# SH08-PWR1.net
KiCad netlist of a schematic drawn in Altium Designer
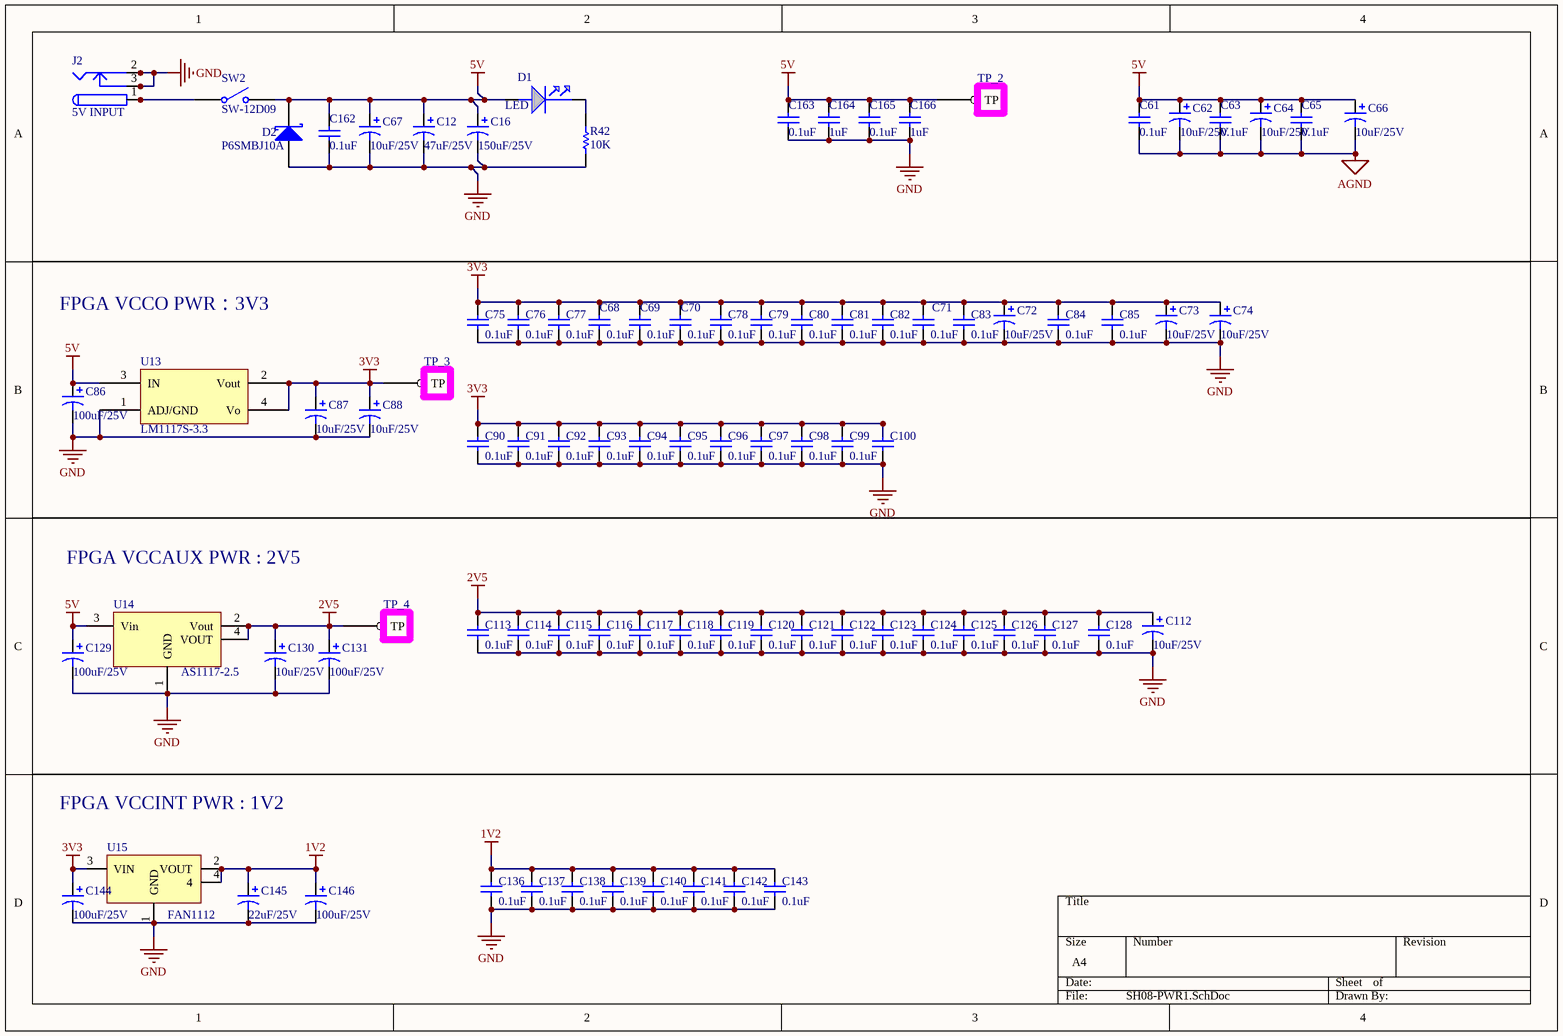
[diagram p0: SH08-PWR1.SchDoc]

(export (version "E")
  (design (tool "Eeschema 10.0.6"))
  (components
    (comp (ref "C12")
      (value "47uF/25V")
      (footprint "1210[3528]")
      (description "Polarized Capacitor (Radial)")
      (fields (field (name "Comment") "Cap Pol,47uF/25V,1210") (field (name "PUBLISHER") "Altium Limited"))
      (libsource (lib "Miscellaneous Devices") (part "Cap Pol1"))
    )
    (comp (ref "C16")
      (value "150uF/25V")
      (footprint "7343")
      (description "Polarized Capacitor (Radial)")
      (fields (field (name "Comment") "Cap Pol,150uF/25V,7343") (field (name "PUBLISHER") "Altium Limited"))
      (libsource (lib "Miscellaneous Devices") (part "Cap Pol1"))
    )
    (comp (ref "C61")
      (value "0.1uF")
      (footprint "1608[0603]")
      (description "Capacitor")
      (fields (field (name "Comment") "Cap,0.1uF/0603") (field (name "PUBLISHER") "Altium Limited"))
      (libsource (lib "Miscellaneous Devices") (part "Cap"))
    )
    (comp (ref "C62")
      (value "10uF/25V")
      (footprint "1206[3216]")
      (description "Polarized Capacitor (Radial)")
      (fields (field (name "Comment") "Cap Pol,10uF/25V,1206") (field (name "PUBLISHER") "Altium Limited"))
      (libsource (lib "Miscellaneous Devices") (part "Cap Pol1"))
    )
    (comp (ref "C63")
      (value "0.1uF")
      (footprint "1608[0603]")
      (description "Capacitor")
      (fields (field (name "Comment") "Cap,0.1uF/0603") (field (name "PUBLISHER") "Altium Limited"))
      (libsource (lib "Miscellaneous Devices") (part "Cap"))
    )
    (comp (ref "C64")
      (value "10uF/25V")
      (footprint "1206[3216]")
      (description "Polarized Capacitor (Radial)")
      (fields (field (name "Comment") "Cap Pol,10uF/25V,1206") (field (name "PUBLISHER") "Altium Limited"))
      (libsource (lib "Miscellaneous Devices") (part "Cap Pol1"))
    )
    (comp (ref "C65")
      (value "0.1uF")
      (footprint "1608[0603]")
      (description "Capacitor")
      (fields (field (name "Comment") "Cap,0.1uF/0603") (field (name "PUBLISHER") "Altium Limited"))
      (libsource (lib "Miscellaneous Devices") (part "Cap"))
    )
    (comp (ref "C66")
      (value "10uF/25V")
      (footprint "1206[3216]")
      (description "Polarized Capacitor (Radial)")
      (fields (field (name "Comment") "Cap Pol,10uF/25V,1206") (field (name "PUBLISHER") "Altium Limited"))
      (libsource (lib "Miscellaneous Devices") (part "Cap Pol1"))
    )
    (comp (ref "C67")
      (value "10uF/25V")
      (footprint "1206[3216]")
      (description "Polarized Capacitor (Radial)")
      (fields (field (name "Comment") "Cap Pol,10uF/25V,1206") (field (name "PUBLISHER") "Altium Limited"))
      (libsource (lib "Miscellaneous Devices") (part "Cap Pol1"))
    )
    (comp (ref "C68")
      (value "0.1uF")
      (footprint "1608[0603]")
      (description "Capacitor")
      (fields (field (name "Comment") "Cap,0.1uF/0603") (field (name "PUBLISHER") "Altium Limited"))
      (libsource (lib "Miscellaneous Devices") (part "Cap"))
    )
    (comp (ref "C69")
      (value "0.1uF")
      (footprint "1608[0603]")
      (description "Capacitor")
      (fields (field (name "Comment") "Cap,0.1uF/0603") (field (name "PUBLISHER") "Altium Limited"))
      (libsource (lib "Miscellaneous Devices") (part "Cap"))
    )
    (comp (ref "C70")
      (value "0.1uF")
      (footprint "1608[0603]")
      (description "Capacitor")
      (fields (field (name "Comment") "Cap,0.1uF/0603") (field (name "PUBLISHER") "Altium Limited"))
      (libsource (lib "Miscellaneous Devices") (part "Cap"))
    )
    (comp (ref "C71")
      (value "0.1uF")
      (footprint "1608[0603]")
      (description "Capacitor")
      (fields (field (name "Comment") "Cap,0.1uF/0603") (field (name "PUBLISHER") "Altium Limited"))
      (libsource (lib "Miscellaneous Devices") (part "Cap"))
    )
    (comp (ref "C72")
      (value "10uF/25V")
      (footprint "1206[3216]")
      (description "Polarized Capacitor (Radial)")
      (fields (field (name "Comment") "Cap Pol,10uF/25V,1206") (field (name "PUBLISHER") "Altium Limited"))
      (libsource (lib "Miscellaneous Devices") (part "Cap Pol1"))
    )
    (comp (ref "C73")
      (value "10uF/25V")
      (footprint "1206[3216]")
      (description "Polarized Capacitor (Radial)")
      (fields (field (name "Comment") "Cap Pol,10uF/25V,1206") (field (name "PUBLISHER") "Altium Limited"))
      (libsource (lib "Miscellaneous Devices") (part "Cap Pol1"))
    )
    (comp (ref "C74")
      (value "10uF/25V")
      (footprint "1206[3216]")
      (description "Polarized Capacitor (Radial)")
      (fields (field (name "Comment") "Cap Pol,10uF/25V,1206") (field (name "PUBLISHER") "Altium Limited"))
      (libsource (lib "Miscellaneous Devices") (part "Cap Pol1"))
    )
    (comp (ref "C75")
      (value "0.1uF")
      (footprint "1608[0603]")
      (description "Capacitor")
      (fields (field (name "Comment") "Cap,0.1uF/0603") (field (name "PUBLISHER") "Altium Limited"))
      (libsource (lib "Miscellaneous Devices") (part "Cap"))
    )
    (comp (ref "C76")
      (value "0.1uF")
      (footprint "1608[0603]")
      (description "Capacitor")
      (fields (field (name "Comment") "Cap,0.1uF/0603") (field (name "PUBLISHER") "Altium Limited"))
      (libsource (lib "Miscellaneous Devices") (part "Cap"))
    )
    (comp (ref "C77")
      (value "0.1uF")
      (footprint "1608[0603]")
      (description "Capacitor")
      (fields (field (name "Comment") "Cap,0.1uF/0603") (field (name "PUBLISHER") "Altium Limited"))
      (libsource (lib "Miscellaneous Devices") (part "Cap"))
    )
    (comp (ref "C78")
      (value "0.1uF")
      (footprint "1608[0603]")
      (description "Capacitor")
      (fields (field (name "Comment") "Cap,0.1uF/0603") (field (name "PUBLISHER") "Altium Limited"))
      (libsource (lib "Miscellaneous Devices") (part "Cap"))
    )
    (comp (ref "C79")
      (value "0.1uF")
      (footprint "1608[0603]")
      (description "Capacitor")
      (fields (field (name "Comment") "Cap,0.1uF/0603") (field (name "PUBLISHER") "Altium Limited"))
      (libsource (lib "Miscellaneous Devices") (part "Cap"))
    )
    (comp (ref "C80")
      (value "0.1uF")
      (footprint "1608[0603]")
      (description "Capacitor")
      (fields (field (name "Comment") "Cap,0.1uF/0603") (field (name "PUBLISHER") "Altium Limited"))
      (libsource (lib "Miscellaneous Devices") (part "Cap"))
    )
    (comp (ref "C81")
      (value "0.1uF")
      (footprint "1608[0603]")
      (description "Capacitor")
      (fields (field (name "Comment") "Cap,0.1uF/0603") (field (name "PUBLISHER") "Altium Limited"))
      (libsource (lib "Miscellaneous Devices") (part "Cap"))
    )
    (comp (ref "C82")
      (value "0.1uF")
      (footprint "1608[0603]")
      (description "Capacitor")
      (fields (field (name "Comment") "Cap,0.1uF/0603") (field (name "PUBLISHER") "Altium Limited"))
      (libsource (lib "Miscellaneous Devices") (part "Cap"))
    )
    (comp (ref "C83")
      (value "0.1uF")
      (footprint "1608[0603]")
      (description "Capacitor")
      (fields (field (name "Comment") "Cap,0.1uF/0603") (field (name "PUBLISHER") "Altium Limited"))
      (libsource (lib "Miscellaneous Devices") (part "Cap"))
    )
    (comp (ref "C84")
      (value "0.1uF")
      (footprint "1608[0603]")
      (description "Capacitor")
      (fields (field (name "Comment") "Cap,0.1uF/0603") (field (name "PUBLISHER") "Altium Limited"))
      (libsource (lib "Miscellaneous Devices") (part "Cap"))
    )
    (comp (ref "C85")
      (value "0.1uF")
      (footprint "1608[0603]")
      (description "Capacitor")
      (fields (field (name "Comment") "Cap,0.1uF/0603") (field (name "PUBLISHER") "Altium Limited"))
      (libsource (lib "Miscellaneous Devices") (part "Cap"))
    )
    (comp (ref "C86")
      (value "100uF/25V")
      (footprint "1210[3528]")
      (description "Polarized Capacitor (Radial)")
      (fields (field (name "Comment") "Cap Pol,100uF/25V,1210") (field (name "PUBLISHER") "Altium Limited"))
      (libsource (lib "Miscellaneous Devices") (part "Cap Pol1"))
    )
    (comp (ref "C87")
      (value "10uF/25V")
      (footprint "1206[3216]")
      (description "Polarized Capacitor (Radial)")
      (fields (field (name "Comment") "Cap Pol,10uF/25V,1206") (field (name "PUBLISHER") "Altium Limited"))
      (libsource (lib "Miscellaneous Devices") (part "Cap Pol1"))
    )
    (comp (ref "C88")
      (value "10uF/25V")
      (footprint "1206[3216]")
      (description "Polarized Capacitor (Radial)")
      (fields (field (name "Comment") "Cap Pol,10uF/25V,1206") (field (name "PUBLISHER") "Altium Limited"))
      (libsource (lib "Miscellaneous Devices") (part "Cap Pol1"))
    )
    (comp (ref "C90")
      (value "0.1uF")
      (footprint "1608[0603]")
      (description "Capacitor")
      (fields (field (name "Comment") "Cap,0.1uF/0603") (field (name "PUBLISHER") "Altium Limited"))
      (libsource (lib "Miscellaneous Devices") (part "Cap"))
    )
    (comp (ref "C91")
      (value "0.1uF")
      (footprint "1608[0603]")
      (description "Capacitor")
      (fields (field (name "Comment") "Cap,0.1uF/0603") (field (name "PUBLISHER") "Altium Limited"))
      (libsource (lib "Miscellaneous Devices") (part "Cap"))
    )
    (comp (ref "C92")
      (value "0.1uF")
      (footprint "1608[0603]")
      (description "Capacitor")
      (fields (field (name "Comment") "Cap,0.1uF/0603") (field (name "PUBLISHER") "Altium Limited"))
      (libsource (lib "Miscellaneous Devices") (part "Cap"))
    )
    (comp (ref "C93")
      (value "0.1uF")
      (footprint "1608[0603]")
      (description "Capacitor")
      (fields (field (name "Comment") "Cap,0.1uF/0603") (field (name "PUBLISHER") "Altium Limited"))
      (libsource (lib "Miscellaneous Devices") (part "Cap"))
    )
    (comp (ref "C94")
      (value "0.1uF")
      (footprint "1608[0603]")
      (description "Capacitor")
      (fields (field (name "Comment") "Cap,0.1uF/0603") (field (name "PUBLISHER") "Altium Limited"))
      (libsource (lib "Miscellaneous Devices") (part "Cap"))
    )
    (comp (ref "C95")
      (value "0.1uF")
      (footprint "1608[0603]")
      (description "Capacitor")
      (fields (field (name "Comment") "Cap,0.1uF/0603") (field (name "PUBLISHER") "Altium Limited"))
      (libsource (lib "Miscellaneous Devices") (part "Cap"))
    )
    (comp (ref "C96")
      (value "0.1uF")
      (footprint "1608[0603]")
      (description "Capacitor")
      (fields (field (name "Comment") "Cap,0.1uF/0603") (field (name "PUBLISHER") "Altium Limited"))
      (libsource (lib "Miscellaneous Devices") (part "Cap"))
    )
    (comp (ref "C97")
      (value "0.1uF")
      (footprint "1608[0603]")
      (description "Capacitor")
      (fields (field (name "Comment") "Cap,0.1uF/0603") (field (name "PUBLISHER") "Altium Limited"))
      (libsource (lib "Miscellaneous Devices") (part "Cap"))
    )
    (comp (ref "C98")
      (value "0.1uF")
      (footprint "1608[0603]")
      (description "Capacitor")
      (fields (field (name "Comment") "Cap,0.1uF/0603") (field (name "PUBLISHER") "Altium Limited"))
      (libsource (lib "Miscellaneous Devices") (part "Cap"))
    )
    (comp (ref "C99")
      (value "0.1uF")
      (footprint "1608[0603]")
      (description "Capacitor")
      (fields (field (name "Comment") "Cap,0.1uF/0603") (field (name "PUBLISHER") "Altium Limited"))
      (libsource (lib "Miscellaneous Devices") (part "Cap"))
    )
    (comp (ref "C100")
      (value "Cap,0.1uF/0603")
      (footprint "1608[0603]")
      (description "Capacitor")
      (fields (field (name "PUBLISHER") "Altium Limited"))
      (libsource (lib "Miscellaneous Devices") (part "Cap"))
    )
    (comp (ref "C112")
      (value "10uF/25V")
      (footprint "1206[3216]")
      (description "Polarized Capacitor (Radial)")
      (fields (field (name "Comment") "Cap Pol,10uF/25V,1206") (field (name "PUBLISHER") "Altium Limited"))
      (libsource (lib "Miscellaneous Devices") (part "Cap Pol1"))
    )
    (comp (ref "C113")
      (value "0.1uF")
      (footprint "1608[0603]")
      (description "Capacitor")
      (fields (field (name "Comment") "Cap,0.1uF/0603") (field (name "PUBLISHER") "Altium Limited"))
      (libsource (lib "Miscellaneous Devices") (part "Cap"))
    )
    (comp (ref "C114")
      (value "0.1uF")
      (footprint "1608[0603]")
      (description "Capacitor")
      (fields (field (name "Comment") "Cap,0.1uF/0603") (field (name "PUBLISHER") "Altium Limited"))
      (libsource (lib "Miscellaneous Devices") (part "Cap"))
    )
    (comp (ref "C115")
      (value "0.1uF")
      (footprint "1608[0603]")
      (description "Capacitor")
      (fields (field (name "Comment") "Cap,0.1uF/0603") (field (name "PUBLISHER") "Altium Limited"))
      (libsource (lib "Miscellaneous Devices") (part "Cap"))
    )
    (comp (ref "C116")
      (value "0.1uF")
      (footprint "1608[0603]")
      (description "Capacitor")
      (fields (field (name "Comment") "Cap,0.1uF/0603") (field (name "PUBLISHER") "Altium Limited"))
      (libsource (lib "Miscellaneous Devices") (part "Cap"))
    )
    (comp (ref "C117")
      (value "0.1uF")
      (footprint "1608[0603]")
      (description "Capacitor")
      (fields (field (name "Comment") "Cap,0.1uF/0603") (field (name "PUBLISHER") "Altium Limited"))
      (libsource (lib "Miscellaneous Devices") (part "Cap"))
    )
    (comp (ref "C118")
      (value "0.1uF")
      (footprint "1608[0603]")
      (description "Capacitor")
      (fields (field (name "Comment") "Cap,0.1uF/0603") (field (name "PUBLISHER") "Altium Limited"))
      (libsource (lib "Miscellaneous Devices") (part "Cap"))
    )
    (comp (ref "C119")
      (value "0.1uF")
      (footprint "1608[0603]")
      (description "Capacitor")
      (fields (field (name "Comment") "Cap,0.1uF/0603") (field (name "PUBLISHER") "Altium Limited"))
      (libsource (lib "Miscellaneous Devices") (part "Cap"))
    )
    (comp (ref "C120")
      (value "0.1uF")
      (footprint "1608[0603]")
      (description "Capacitor")
      (fields (field (name "Comment") "Cap,0.1uF/0603") (field (name "PUBLISHER") "Altium Limited"))
      (libsource (lib "Miscellaneous Devices") (part "Cap"))
    )
    (comp (ref "C121")
      (value "0.1uF")
      (footprint "1608[0603]")
      (description "Capacitor")
      (fields (field (name "Comment") "Cap,0.1uF/0603") (field (name "PUBLISHER") "Altium Limited"))
      (libsource (lib "Miscellaneous Devices") (part "Cap"))
    )
    (comp (ref "C122")
      (value "0.1uF")
      (footprint "1608[0603]")
      (description "Capacitor")
      (fields (field (name "Comment") "Cap,0.1uF/0603") (field (name "PUBLISHER") "Altium Limited"))
      (libsource (lib "Miscellaneous Devices") (part "Cap"))
    )
    (comp (ref "C123")
      (value "0.1uF")
      (footprint "1608[0603]")
      (description "Capacitor")
      (fields (field (name "Comment") "Cap,0.1uF/0603") (field (name "PUBLISHER") "Altium Limited"))
      (libsource (lib "Miscellaneous Devices") (part "Cap"))
    )
    (comp (ref "C124")
      (value "0.1uF")
      (footprint "1608[0603]")
      (description "Capacitor")
      (fields (field (name "Comment") "Cap,0.1uF/0603") (field (name "PUBLISHER") "Altium Limited"))
      (libsource (lib "Miscellaneous Devices") (part "Cap"))
    )
    (comp (ref "C125")
      (value "0.1uF")
      (footprint "1608[0603]")
      (description "Capacitor")
      (fields (field (name "Comment") "Cap,0.1uF/0603") (field (name "PUBLISHER") "Altium Limited"))
      (libsource (lib "Miscellaneous Devices") (part "Cap"))
    )
    (comp (ref "C126")
      (value "0.1uF")
      (footprint "1608[0603]")
      (description "Capacitor")
      (fields (field (name "Comment") "Cap,0.1uF/0603") (field (name "PUBLISHER") "Altium Limited"))
      (libsource (lib "Miscellaneous Devices") (part "Cap"))
    )
    (comp (ref "C127")
      (value "0.1uF")
      (footprint "1608[0603]")
      (description "Capacitor")
      (fields (field (name "Comment") "Cap,0.1uF/0603") (field (name "PUBLISHER") "Altium Limited"))
      (libsource (lib "Miscellaneous Devices") (part "Cap"))
    )
    (comp (ref "C128")
      (value "0.1uF")
      (footprint "1608[0603]")
      (description "Capacitor")
      (fields (field (name "Comment") "Cap,0.1uF/0603") (field (name "PUBLISHER") "Altium Limited"))
      (libsource (lib "Miscellaneous Devices") (part "Cap"))
    )
    (comp (ref "C129")
      (value "100uF/25V")
      (footprint "1210[3528]")
      (description "Polarized Capacitor (Radial)")
      (fields (field (name "Comment") "Cap Pol,100uF/25V,1210") (field (name "PUBLISHER") "Altium Limited"))
      (libsource (lib "Miscellaneous Devices") (part "Cap Pol1"))
    )
    (comp (ref "C130")
      (value "10uF/25V")
      (footprint "1206[3216]")
      (description "Polarized Capacitor (Radial)")
      (fields (field (name "Comment") "Cap Pol,10uF/25V,1206") (field (name "PUBLISHER") "Altium Limited"))
      (libsource (lib "Miscellaneous Devices") (part "Cap Pol1"))
    )
    (comp (ref "C131")
      (value "100uF/25V")
      (footprint "1210[3528]")
      (description "Polarized Capacitor (Radial)")
      (fields (field (name "Comment") "Cap Pol,100uF/25V,1210") (field (name "PUBLISHER") "Altium Limited"))
      (libsource (lib "Miscellaneous Devices") (part "Cap Pol1"))
    )
    (comp (ref "C136")
      (value "0.1uF")
      (footprint "1608[0603]")
      (description "Capacitor")
      (fields (field (name "Comment") "Cap,0.1uF/0603") (field (name "PUBLISHER") "Altium Limited"))
      (libsource (lib "Miscellaneous Devices") (part "Cap"))
    )
    (comp (ref "C137")
      (value "0.1uF")
      (footprint "1608[0603]")
      (description "Capacitor")
      (fields (field (name "Comment") "Cap,0.1uF/0603") (field (name "PUBLISHER") "Altium Limited"))
      (libsource (lib "Miscellaneous Devices") (part "Cap"))
    )
    (comp (ref "C138")
      (value "0.1uF")
      (footprint "1608[0603]")
      (description "Capacitor")
      (fields (field (name "Comment") "Cap,0.1uF/0603") (field (name "PUBLISHER") "Altium Limited"))
      (libsource (lib "Miscellaneous Devices") (part "Cap"))
    )
    (comp (ref "C139")
      (value "0.1uF")
      (footprint "1608[0603]")
      (description "Capacitor")
      (fields (field (name "Comment") "Cap,0.1uF/0603") (field (name "PUBLISHER") "Altium Limited"))
      (libsource (lib "Miscellaneous Devices") (part "Cap"))
    )
    (comp (ref "C140")
      (value "0.1uF")
      (footprint "1608[0603]")
      (description "Capacitor")
      (fields (field (name "Comment") "Cap,0.1uF/0603") (field (name "PUBLISHER") "Altium Limited"))
      (libsource (lib "Miscellaneous Devices") (part "Cap"))
    )
    (comp (ref "C141")
      (value "0.1uF")
      (footprint "1608[0603]")
      (description "Capacitor")
      (fields (field (name "Comment") "Cap,0.1uF/0603") (field (name "PUBLISHER") "Altium Limited"))
      (libsource (lib "Miscellaneous Devices") (part "Cap"))
    )
    (comp (ref "C142")
      (value "0.1uF")
      (footprint "1608[0603]")
      (description "Capacitor")
      (fields (field (name "Comment") "Cap,0.1uF/0603") (field (name "PUBLISHER") "Altium Limited"))
      (libsource (lib "Miscellaneous Devices") (part "Cap"))
    )
    (comp (ref "C143")
      (value "0.1uF")
      (footprint "1608[0603]")
      (description "Capacitor")
      (fields (field (name "Comment") "Cap,0.1uF/0603") (field (name "PUBLISHER") "Altium Limited"))
      (libsource (lib "Miscellaneous Devices") (part "Cap"))
    )
    (comp (ref "C144")
      (value "100uF/25V")
      (footprint "1210[3528]")
      (description "Polarized Capacitor (Radial)")
      (fields (field (name "Comment") "Cap Pol,100uF/25V,1210") (field (name "PUBLISHER") "Altium Limited"))
      (libsource (lib "Miscellaneous Devices") (part "Cap Pol1"))
    )
    (comp (ref "C145")
      (value "22uF/25V")
      (footprint "1210[3528]")
      (description "Polarized Capacitor (Radial)")
      (fields (field (name "Comment") "Cap Pol,22uF/25V,1210") (field (name "PUBLISHER") "Altium Limited"))
      (libsource (lib "Miscellaneous Devices") (part "Cap Pol1"))
    )
    (comp (ref "C146")
      (value "100uF/25V")
      (footprint "1210[3528]")
      (description "Polarized Capacitor (Radial)")
      (fields (field (name "Comment") "Cap Pol,100uF/25V,1210") (field (name "PUBLISHER") "Altium Limited"))
      (libsource (lib "Miscellaneous Devices") (part "Cap Pol1"))
    )
    (comp (ref "C162")
      (value "0.1uF")
      (footprint "1608[0603]")
      (description "Capacitor")
      (fields (field (name "Comment") "Cap,0.1uF/0603") (field (name "PUBLISHER") "Altium Limited"))
      (libsource (lib "Miscellaneous Devices") (part "Cap"))
    )
    (comp (ref "C163")
      (value "0.1uF")
      (footprint "1608[0603]")
      (description "Capacitor")
      (fields (field (name "Comment") "Cap,0.1uF/0603") (field (name "PUBLISHER") "Altium Limited"))
      (libsource (lib "Miscellaneous Devices") (part "Cap"))
    )
    (comp (ref "C164")
      (value "1uF")
      (footprint "2012[0805]")
      (description "Capacitor")
      (fields (field (name "Comment") "Cap,1uF/0805") (field (name "PUBLISHER") "Altium Limited"))
      (libsource (lib "Miscellaneous Devices") (part "Cap"))
    )
    (comp (ref "C165")
      (value "0.1uF")
      (footprint "1608[0603]")
      (description "Capacitor")
      (fields (field (name "Comment") "Cap,0.1uF/0603") (field (name "PUBLISHER") "Altium Limited"))
      (libsource (lib "Miscellaneous Devices") (part "Cap"))
    )
    (comp (ref "C166")
      (value "1uF")
      (footprint "2012[0805]")
      (description "Capacitor")
      (fields (field (name "Comment") "Cap,1uF/0805") (field (name "PUBLISHER") "Altium Limited"))
      (libsource (lib "Miscellaneous Devices") (part "Cap"))
    )
    (comp (ref "D1")
      (value "LED")
      (footprint "Laser-LiuXin:2012[0805] - LED")
      (libsource (lib "Mylibrary") (part "LED"))
    )
    (comp (ref "D2")
      (value "P6SMBJ10A")
      (footprint "Laser-LiuXin:SMBJ10A_DIOM4336X24N")
      (description "Schottky Rectifier")
      (fields (field (name "PUBLISHER") "Altium Limited"))
      (libsource (lib "Miscellaneous Devices") (part "Diode 11DQ03"))
    )
    (comp (ref "J2")
      (value "5V INPUT")
      (footprint "Laser-LiuXin:IF_KLD-0202")
      (description "Low Voltage Power Supply Connector")
      (fields (field (name "PUBLISHER") "Altium Limited"))
      (libsource (lib "Miscellaneous Connectors") (part "PWR2.5"))
    )
    (comp (ref "R42")
      (value "10K")
      (footprint "Laser-LiuXin:1608[0603]")
      (description "Resistor")
      (fields (field (name "Comment") "Res,10K/0603") (field (name "PUBLISHER") "Altium Limited"))
      (libsource (lib "Miscellaneous Devices") (part "Res1"))
    )
    (comp (ref "SW2")
      (value "SW-12D09")
      (footprint "SW_SD12D09")
      (description "Single-Pole, Single-Throw Switch")
      (fields (field (name "PUBLISHER") "Altium Limited"))
      (libsource (lib "Miscellaneous Devices") (part "SW-SPST"))
    )
    (comp (ref "TP_2") (value "5V") (footprint "MYTP") (libsource (lib "*") (part "TEST POINT_0")))
    (comp (ref "TP_3") (value "3V3") (footprint "MYTP") (libsource (lib "*") (part "TEST POINT_0")))
    (comp (ref "TP_4") (value "2V5") (footprint "MYTP") (libsource (lib "*") (part "TEST POINT_0")))
    (comp (ref "U13")
      (value "LM1117S-3.3")
      (footprint "Laser-LiuXin:TO-263-3SMD")
      (libsource (lib "Laser-LiuXin") (part "PWR_LM1117S-3.3"))
    )
    (comp (ref "U14")
      (value "AS1117-2.5")
      (footprint "SOT223P700X180-4N")
      (libsource (lib "Mylibrary") (part "VOLTREG"))
    )
    (comp (ref "U15")
      (value "FAN1112")
      (footprint "SOT-223(FAN1112)")
      (libsource (lib "PCB_Project_FPGA_aquisition") (part "FAN1112"))
    )
  )
  (nets
    (net (code "1") (name "1V2") (class "Default")
      (node (ref "C136") (pin "2") (pinfunction "2_2") (pintype "passive"))
      (node (ref "C137") (pin "2") (pinfunction "2_2") (pintype "passive"))
      (node (ref "C138") (pin "2") (pinfunction "2_2") (pintype "passive"))
      (node (ref "C139") (pin "2") (pinfunction "2_2") (pintype "passive"))
      (node (ref "C140") (pin "2") (pinfunction "2_2") (pintype "passive"))
      (node (ref "C141") (pin "2") (pinfunction "2_2") (pintype "passive"))
      (node (ref "C142") (pin "2") (pinfunction "2_2") (pintype "passive"))
      (node (ref "C143") (pin "2") (pinfunction "2_2") (pintype "passive"))
      (node (ref "C145") (pin "1") (pinfunction "1_1") (pintype "passive"))
      (node (ref "C146") (pin "1") (pinfunction "1_1") (pintype "passive"))
      (node (ref "U15") (pin "2") (pinfunction "VOUT_2") (pintype "passive"))
      (node (ref "U15") (pin "4") (pinfunction "4_4") (pintype "passive"))
    )
    (net (code "2") (name "2V5") (class "Default")
      (node (ref "C112") (pin "1") (pinfunction "1_1") (pintype "passive"))
      (node (ref "C113") (pin "2") (pinfunction "2_2") (pintype "passive"))
      (node (ref "C114") (pin "2") (pinfunction "2_2") (pintype "passive"))
      (node (ref "C115") (pin "2") (pinfunction "2_2") (pintype "passive"))
      (node (ref "C116") (pin "2") (pinfunction "2_2") (pintype "passive"))
      (node (ref "C117") (pin "2") (pinfunction "2_2") (pintype "passive"))
      (node (ref "C118") (pin "2") (pinfunction "2_2") (pintype "passive"))
      (node (ref "C119") (pin "2") (pinfunction "2_2") (pintype "passive"))
      (node (ref "C120") (pin "2") (pinfunction "2_2") (pintype "passive"))
      (node (ref "C121") (pin "2") (pinfunction "2_2") (pintype "passive"))
      (node (ref "C122") (pin "2") (pinfunction "2_2") (pintype "passive"))
      (node (ref "C123") (pin "2") (pinfunction "2_2") (pintype "passive"))
      (node (ref "C124") (pin "2") (pinfunction "2_2") (pintype "passive"))
      (node (ref "C125") (pin "2") (pinfunction "2_2") (pintype "passive"))
      (node (ref "C126") (pin "2") (pinfunction "2_2") (pintype "passive"))
      (node (ref "C127") (pin "2") (pinfunction "2_2") (pintype "passive"))
      (node (ref "C128") (pin "2") (pinfunction "2_2") (pintype "passive"))
      (node (ref "C130") (pin "1") (pinfunction "1_1") (pintype "passive"))
      (node (ref "C131") (pin "1") (pinfunction "1_1") (pintype "passive"))
      (node (ref "TP_4") (pin "1") (pinfunction "TP_1") (pintype "passive"))
      (node (ref "U14") (pin "2") (pinfunction "Vout_2") (pintype "passive"))
      (node (ref "U14") (pin "4") (pinfunction "VOUT_4") (pintype "passive"))
    )
    (net (code "3") (name "3V3") (class "Default")
      (node (ref "C100") (pin "2") (pinfunction "2_2") (pintype "passive"))
      (node (ref "C144") (pin "1") (pinfunction "1_1") (pintype "passive"))
      (node (ref "C68") (pin "2") (pinfunction "2_2") (pintype "passive"))
      (node (ref "C69") (pin "2") (pinfunction "2_2") (pintype "passive"))
      (node (ref "C70") (pin "2") (pinfunction "2_2") (pintype "passive"))
      (node (ref "C71") (pin "2") (pinfunction "2_2") (pintype "passive"))
      (node (ref "C72") (pin "1") (pinfunction "1_1") (pintype "passive"))
      (node (ref "C73") (pin "1") (pinfunction "1_1") (pintype "passive"))
      (node (ref "C74") (pin "1") (pinfunction "1_1") (pintype "passive"))
      (node (ref "C75") (pin "2") (pinfunction "2_2") (pintype "passive"))
      (node (ref "C76") (pin "2") (pinfunction "2_2") (pintype "passive"))
      (node (ref "C77") (pin "2") (pinfunction "2_2") (pintype "passive"))
      (node (ref "C78") (pin "2") (pinfunction "2_2") (pintype "passive"))
      (node (ref "C79") (pin "2") (pinfunction "2_2") (pintype "passive"))
      (node (ref "C80") (pin "2") (pinfunction "2_2") (pintype "passive"))
      (node (ref "C81") (pin "2") (pinfunction "2_2") (pintype "passive"))
      (node (ref "C82") (pin "2") (pinfunction "2_2") (pintype "passive"))
      (node (ref "C83") (pin "2") (pinfunction "2_2") (pintype "passive"))
      (node (ref "C84") (pin "2") (pinfunction "2_2") (pintype "passive"))
      (node (ref "C85") (pin "2") (pinfunction "2_2") (pintype "passive"))
      (node (ref "C87") (pin "1") (pinfunction "1_1") (pintype "passive"))
      (node (ref "C88") (pin "1") (pinfunction "1_1") (pintype "passive"))
      (node (ref "C90") (pin "2") (pinfunction "2_2") (pintype "passive"))
      (node (ref "C91") (pin "2") (pinfunction "2_2") (pintype "passive"))
      (node (ref "C92") (pin "2") (pinfunction "2_2") (pintype "passive"))
      (node (ref "C93") (pin "2") (pinfunction "2_2") (pintype "passive"))
      (node (ref "C94") (pin "2") (pinfunction "2_2") (pintype "passive"))
      (node (ref "C95") (pin "2") (pinfunction "2_2") (pintype "passive"))
      (node (ref "C96") (pin "2") (pinfunction "2_2") (pintype "passive"))
      (node (ref "C97") (pin "2") (pinfunction "2_2") (pintype "passive"))
      (node (ref "C98") (pin "2") (pinfunction "2_2") (pintype "passive"))
      (node (ref "C99") (pin "2") (pinfunction "2_2") (pintype "passive"))
      (node (ref "TP_3") (pin "1") (pinfunction "TP_1") (pintype "passive"))
      (node (ref "U13") (pin "2") (pinfunction "Vout_2") (pintype "power_in"))
      (node (ref "U13") (pin "4") (pinfunction "Vo_4") (pintype "power_in"))
      (node (ref "U15") (pin "3") (pinfunction "VIN_3") (pintype "passive"))
    )
    (net (code "4") (name "5V") (class "Default")
      (node (ref "C12") (pin "1") (pinfunction "1_1") (pintype "passive"))
      (node (ref "C129") (pin "1") (pinfunction "1_1") (pintype "passive"))
      (node (ref "C16") (pin "1") (pinfunction "1_1") (pintype "passive"))
      (node (ref "C162") (pin "1") (pinfunction "1_1") (pintype "passive"))
      (node (ref "C163") (pin "1") (pinfunction "1_1") (pintype "passive"))
      (node (ref "C164") (pin "1") (pinfunction "1_1") (pintype "passive"))
      (node (ref "C165") (pin "1") (pinfunction "1_1") (pintype "passive"))
      (node (ref "C166") (pin "1") (pinfunction "1_1") (pintype "passive"))
      (node (ref "C61") (pin "1") (pinfunction "1_1") (pintype "passive"))
      (node (ref "C62") (pin "1") (pinfunction "1_1") (pintype "passive"))
      (node (ref "C63") (pin "1") (pinfunction "1_1") (pintype "passive"))
      (node (ref "C64") (pin "1") (pinfunction "1_1") (pintype "passive"))
      (node (ref "C65") (pin "1") (pinfunction "1_1") (pintype "passive"))
      (node (ref "C66") (pin "1") (pinfunction "1_1") (pintype "passive"))
      (node (ref "C67") (pin "1") (pinfunction "1_1") (pintype "passive"))
      (node (ref "C86") (pin "1") (pinfunction "1_1") (pintype "passive"))
      (node (ref "D1") (pin "1") (pinfunction "1_1") (pintype "passive"))
      (node (ref "D2") (pin "2") (pinfunction "K_2") (pintype "passive"))
      (node (ref "SW2") (pin "2") (pinfunction "NO_2") (pintype "passive"))
      (node (ref "TP_2") (pin "1") (pinfunction "TP_1") (pintype "passive"))
      (node (ref "U13") (pin "3") (pinfunction "IN_3") (pintype "power_in"))
      (node (ref "U14") (pin "3") (pinfunction "Vin_3") (pintype "passive"))
    )
    (net (code "5") (name "AGND") (class "Default")
      (node (ref "C61") (pin "2") (pinfunction "2_2") (pintype "passive"))
      (node (ref "C62") (pin "2") (pinfunction "2_2") (pintype "passive"))
      (node (ref "C63") (pin "2") (pinfunction "2_2") (pintype "passive"))
      (node (ref "C64") (pin "2") (pinfunction "2_2") (pintype "passive"))
      (node (ref "C65") (pin "2") (pinfunction "2_2") (pintype "passive"))
      (node (ref "C66") (pin "2") (pinfunction "2_2") (pintype "passive"))
    )
    (net (code "6") (name "GND") (class "Default")
      (node (ref "C100") (pin "1") (pinfunction "1_1") (pintype "passive"))
      (node (ref "C112") (pin "2") (pinfunction "2_2") (pintype "passive"))
      (node (ref "C113") (pin "1") (pinfunction "1_1") (pintype "passive"))
      (node (ref "C114") (pin "1") (pinfunction "1_1") (pintype "passive"))
      (node (ref "C115") (pin "1") (pinfunction "1_1") (pintype "passive"))
      (node (ref "C116") (pin "1") (pinfunction "1_1") (pintype "passive"))
      (node (ref "C117") (pin "1") (pinfunction "1_1") (pintype "passive"))
      (node (ref "C118") (pin "1") (pinfunction "1_1") (pintype "passive"))
      (node (ref "C119") (pin "1") (pinfunction "1_1") (pintype "passive"))
      (node (ref "C12") (pin "2") (pinfunction "2_2") (pintype "passive"))
      (node (ref "C120") (pin "1") (pinfunction "1_1") (pintype "passive"))
      (node (ref "C121") (pin "1") (pinfunction "1_1") (pintype "passive"))
      (node (ref "C122") (pin "1") (pinfunction "1_1") (pintype "passive"))
      (node (ref "C123") (pin "1") (pinfunction "1_1") (pintype "passive"))
      (node (ref "C124") (pin "1") (pinfunction "1_1") (pintype "passive"))
      (node (ref "C125") (pin "1") (pinfunction "1_1") (pintype "passive"))
      (node (ref "C126") (pin "1") (pinfunction "1_1") (pintype "passive"))
      (node (ref "C127") (pin "1") (pinfunction "1_1") (pintype "passive"))
      (node (ref "C128") (pin "1") (pinfunction "1_1") (pintype "passive"))
      (node (ref "C129") (pin "2") (pinfunction "2_2") (pintype "passive"))
      (node (ref "C130") (pin "2") (pinfunction "2_2") (pintype "passive"))
      (node (ref "C131") (pin "2") (pinfunction "2_2") (pintype "passive"))
      (node (ref "C136") (pin "1") (pinfunction "1_1") (pintype "passive"))
      (node (ref "C137") (pin "1") (pinfunction "1_1") (pintype "passive"))
      (node (ref "C138") (pin "1") (pinfunction "1_1") (pintype "passive"))
      (node (ref "C139") (pin "1") (pinfunction "1_1") (pintype "passive"))
      (node (ref "C140") (pin "1") (pinfunction "1_1") (pintype "passive"))
      (node (ref "C141") (pin "1") (pinfunction "1_1") (pintype "passive"))
      (node (ref "C142") (pin "1") (pinfunction "1_1") (pintype "passive"))
      (node (ref "C143") (pin "1") (pinfunction "1_1") (pintype "passive"))
      (node (ref "C144") (pin "2") (pinfunction "2_2") (pintype "passive"))
      (node (ref "C145") (pin "2") (pinfunction "2_2") (pintype "passive"))
      (node (ref "C146") (pin "2") (pinfunction "2_2") (pintype "passive"))
      (node (ref "C16") (pin "2") (pinfunction "2_2") (pintype "passive"))
      (node (ref "C162") (pin "2") (pinfunction "2_2") (pintype "passive"))
      (node (ref "C163") (pin "2") (pinfunction "2_2") (pintype "passive"))
      (node (ref "C164") (pin "2") (pinfunction "2_2") (pintype "passive"))
      (node (ref "C165") (pin "2") (pinfunction "2_2") (pintype "passive"))
      (node (ref "C166") (pin "2") (pinfunction "2_2") (pintype "passive"))
      (node (ref "C67") (pin "2") (pinfunction "2_2") (pintype "passive"))
      (node (ref "C68") (pin "1") (pinfunction "1_1") (pintype "passive"))
      (node (ref "C69") (pin "1") (pinfunction "1_1") (pintype "passive"))
      (node (ref "C70") (pin "1") (pinfunction "1_1") (pintype "passive"))
      (node (ref "C71") (pin "1") (pinfunction "1_1") (pintype "passive"))
      (node (ref "C72") (pin "2") (pinfunction "2_2") (pintype "passive"))
      (node (ref "C73") (pin "2") (pinfunction "2_2") (pintype "passive"))
      (node (ref "C74") (pin "2") (pinfunction "2_2") (pintype "passive"))
      (node (ref "C75") (pin "1") (pinfunction "1_1") (pintype "passive"))
      (node (ref "C76") (pin "1") (pinfunction "1_1") (pintype "passive"))
      (node (ref "C77") (pin "1") (pinfunction "1_1") (pintype "passive"))
      (node (ref "C78") (pin "1") (pinfunction "1_1") (pintype "passive"))
      (node (ref "C79") (pin "1") (pinfunction "1_1") (pintype "passive"))
      (node (ref "C80") (pin "1") (pinfunction "1_1") (pintype "passive"))
      (node (ref "C81") (pin "1") (pinfunction "1_1") (pintype "passive"))
      (node (ref "C82") (pin "1") (pinfunction "1_1") (pintype "passive"))
      (node (ref "C83") (pin "1") (pinfunction "1_1") (pintype "passive"))
      (node (ref "C84") (pin "1") (pinfunction "1_1") (pintype "passive"))
      (node (ref "C85") (pin "1") (pinfunction "1_1") (pintype "passive"))
      (node (ref "C86") (pin "2") (pinfunction "2_2") (pintype "passive"))
      (node (ref "C87") (pin "2") (pinfunction "2_2") (pintype "passive"))
      (node (ref "C88") (pin "2") (pinfunction "2_2") (pintype "passive"))
      (node (ref "C90") (pin "1") (pinfunction "1_1") (pintype "passive"))
      (node (ref "C91") (pin "1") (pinfunction "1_1") (pintype "passive"))
      (node (ref "C92") (pin "1") (pinfunction "1_1") (pintype "passive"))
      (node (ref "C93") (pin "1") (pinfunction "1_1") (pintype "passive"))
      (node (ref "C94") (pin "1") (pinfunction "1_1") (pintype "passive"))
      (node (ref "C95") (pin "1") (pinfunction "1_1") (pintype "passive"))
      (node (ref "C96") (pin "1") (pinfunction "1_1") (pintype "passive"))
      (node (ref "C97") (pin "1") (pinfunction "1_1") (pintype "passive"))
      (node (ref "C98") (pin "1") (pinfunction "1_1") (pintype "passive"))
      (node (ref "C99") (pin "1") (pinfunction "1_1") (pintype "passive"))
      (node (ref "D2") (pin "1") (pinfunction "A_1") (pintype "passive"))
      (node (ref "J2") (pin "2") (pinfunction "2_2") (pintype "power_in"))
      (node (ref "J2") (pin "2A") (pinfunction "2A_2A") (pintype "power_in"))
      (node (ref "J2") (pin "2B") (pinfunction "2B_2B") (pintype "power_in"))
      (node (ref "J2") (pin "3") (pinfunction "3_3") (pintype "power_in"))
      (node (ref "J2") (pin "3A") (pinfunction "3A_3A") (pintype "power_in"))
      (node (ref "J2") (pin "3B") (pinfunction "3B_3B") (pintype "power_in"))
      (node (ref "R42") (pin "1") (pinfunction "1_1") (pintype "passive"))
      (node (ref "U13") (pin "1") (pinfunction "ADJ/GND_1") (pintype "power_in"))
      (node (ref "U14") (pin "1") (pinfunction "GND_1") (pintype "passive"))
      (node (ref "U15") (pin "1") (pinfunction "GND_1") (pintype "passive"))
    )
    (net (code "7") (name "Net-(D1-Pad2)") (class "Default")
      (node (ref "D1") (pin "2") (pinfunction "2_2") (pintype "passive"))
      (node (ref "R42") (pin "2") (pinfunction "2_2") (pintype "passive"))
    )
    (net (code "8") (name "Net-(SW2-COMMON)") (class "Default")
      (node (ref "J2") (pin "1") (pinfunction "1_1") (pintype "power_in"))
      (node (ref "J2") (pin "1A") (pinfunction "1A_1A") (pintype "power_in"))
      (node (ref "J2") (pin "1B") (pinfunction "1B_1B") (pintype "power_in"))
      (node (ref "SW2") (pin "1") (pinfunction "COMMON_1") (pintype "passive"))
    )
  )
)
